# RPi_Bowler_Port.net
KiCad netlist of a schematic drawn in Altium Designer
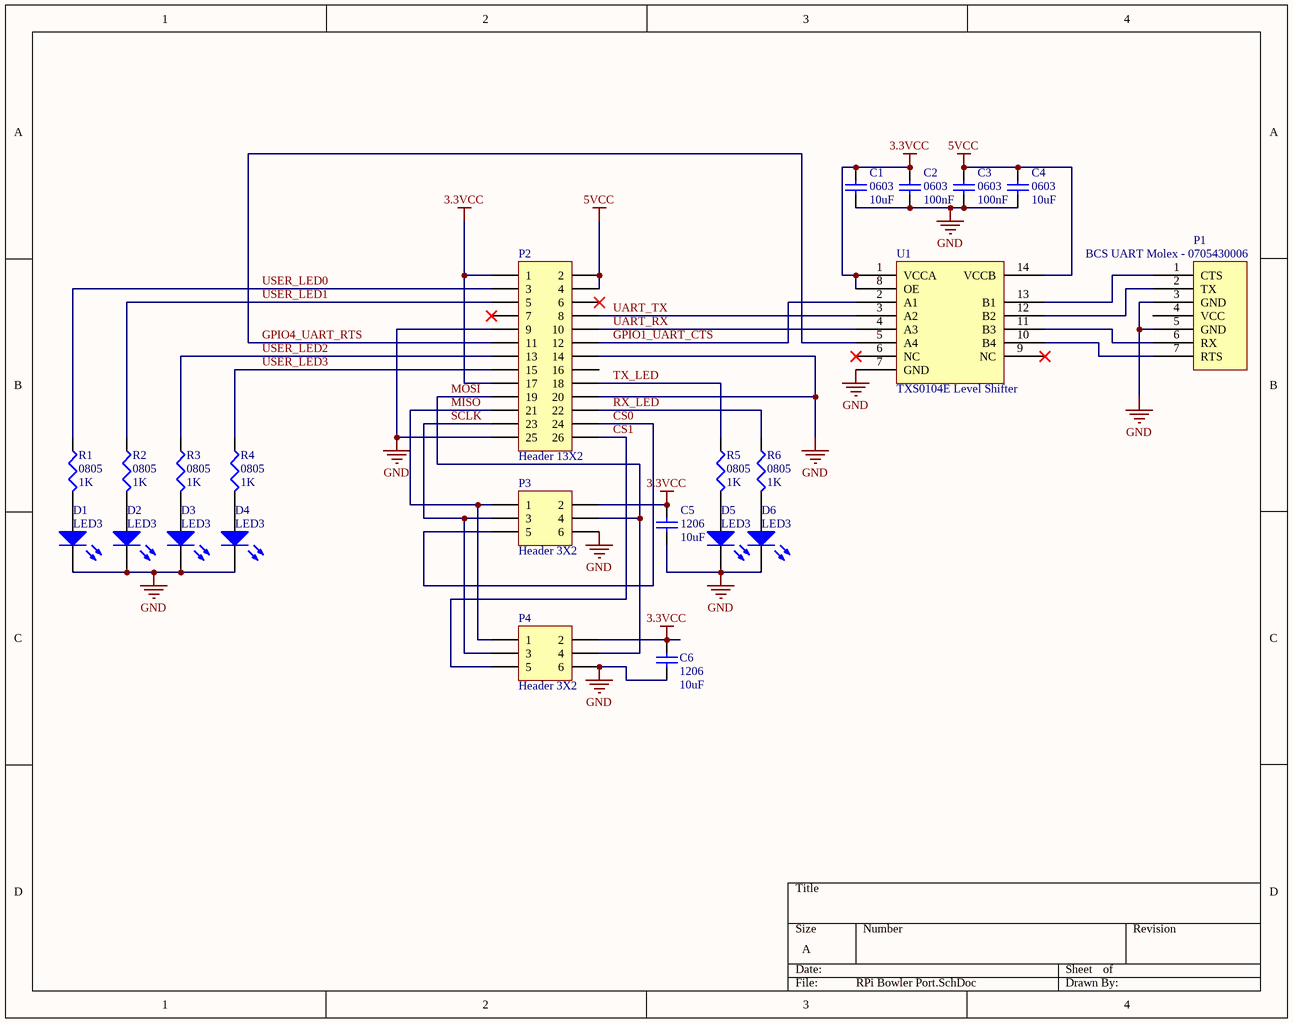
[diagram p0: RPi Bowler Port.SchDoc]

(export (version "E")
  (design (tool "Eeschema 10.0.6"))
  (components
    (comp (ref "C1")
      (value "0603")
      (footprint "1608[0603]")
      (description "Capacitor (Semiconductor SIM Model)")
      (fields (field (name "ALTIUM_VALUE") "10uF") (field (name "PUBLISHER") "Altium Limited"))
      (libsource (lib "Miscellaneous Devices") (part "Cap Semi"))
    )
    (comp (ref "C2")
      (value "0603")
      (footprint "1608[0603]")
      (description "Capacitor (Semiconductor SIM Model)")
      (fields (field (name "ALTIUM_VALUE") "100nF") (field (name "PUBLISHER") "Altium Limited"))
      (libsource (lib "Miscellaneous Devices") (part "Cap Semi"))
    )
    (comp (ref "C3")
      (value "0603")
      (footprint "1608[0603]")
      (description "Capacitor (Semiconductor SIM Model)")
      (fields (field (name "ALTIUM_VALUE") "100nF") (field (name "PUBLISHER") "Altium Limited"))
      (libsource (lib "Miscellaneous Devices") (part "Cap Semi"))
    )
    (comp (ref "C4")
      (value "0603")
      (footprint "1608[0603]")
      (description "Capacitor (Semiconductor SIM Model)")
      (fields (field (name "ALTIUM_VALUE") "10uF") (field (name "PUBLISHER") "Altium Limited"))
      (libsource (lib "Miscellaneous Devices") (part "Cap Semi"))
    )
    (comp (ref "C5")
      (value "1206")
      (footprint "C1206")
      (description "Capacitor (Semiconductor SIM Model)")
      (fields (field (name "ALTIUM_VALUE") "10uF") (field (name "PUBLISHER") "Altium Limited"))
      (libsource (lib "Miscellaneous Devices") (part "Cap Semi"))
    )
    (comp (ref "C6")
      (value "1206")
      (footprint "C1206")
      (description "Capacitor (Semiconductor SIM Model)")
      (fields (field (name "ALTIUM_VALUE") "10uF") (field (name "PUBLISHER") "Altium Limited"))
      (libsource (lib "Miscellaneous Devices") (part "Cap Semi"))
    )
    (comp (ref "D1")
      (value "LED3")
      (footprint "SM 0805 polarized")
      (description "Typical BLUE SiC LED")
      (fields (field (name "PUBLISHER") "Altium Limited"))
      (libsource (lib "Miscellaneous Devices") (part "LED3"))
    )
    (comp (ref "D2")
      (value "LED3")
      (footprint "SM 0805 polarized")
      (description "Typical BLUE SiC LED")
      (fields (field (name "PUBLISHER") "Altium Limited"))
      (libsource (lib "Miscellaneous Devices") (part "LED3"))
    )
    (comp (ref "D3")
      (value "LED3")
      (footprint "SM 0805 polarized")
      (description "Typical BLUE SiC LED")
      (fields (field (name "PUBLISHER") "Altium Limited"))
      (libsource (lib "Miscellaneous Devices") (part "LED3"))
    )
    (comp (ref "D4")
      (value "LED3")
      (footprint "SM 0805 polarized")
      (description "Typical BLUE SiC LED")
      (fields (field (name "PUBLISHER") "Altium Limited"))
      (libsource (lib "Miscellaneous Devices") (part "LED3"))
    )
    (comp (ref "D5")
      (value "LED3")
      (footprint "SM 0805 polarized")
      (description "Typical BLUE SiC LED")
      (fields (field (name "PUBLISHER") "Altium Limited"))
      (libsource (lib "Miscellaneous Devices") (part "LED3"))
    )
    (comp (ref "D6")
      (value "LED3")
      (footprint "SM 0805 polarized")
      (description "Typical BLUE SiC LED")
      (fields (field (name "PUBLISHER") "Altium Limited"))
      (libsource (lib "Miscellaneous Devices") (part "LED3"))
    )
    (comp (ref "P1")
      (value "BCS UART Molex - 0705430006")
      (footprint "BCS Serial Port - Molex")
      (description "BCS UART Port Molex")
      (libsource (lib "RPi Bowler Symbol Lib") (part "BCS Serial Port - Molex"))
    )
    (comp (ref "P2")
      (value "Header 13X2")
      (footprint "HDR2X13")
      (description "Header, 13-Pin, Dual row")
      (fields (field (name "PUBLISHER") "Altium Limited"))
      (libsource (lib "Miscellaneous Connectors") (part "Header 13X2"))
    )
    (comp (ref "P3")
      (value "Header 3X2")
      (footprint "HDR2X3")
      (description "Header, 3-Pin, Dual row")
      (fields (field (name "PUBLISHER") "Altium Limited"))
      (libsource (lib "Miscellaneous Connectors") (part "Header 3X2"))
    )
    (comp (ref "P4")
      (value "Header 3X2")
      (footprint "HDR2X3")
      (description "Header, 3-Pin, Dual row")
      (fields (field (name "PUBLISHER") "Altium Limited"))
      (libsource (lib "Miscellaneous Connectors") (part "Header 3X2"))
    )
    (comp (ref "R1")
      (value "0805")
      (footprint "SM 0805 - gap trimmed")
      (description "Resistor")
      (fields (field (name "ALTIUM_VALUE") "1K") (field (name "PUBLISHER") "Altium Limited"))
      (libsource (lib "Miscellaneous Devices") (part "Res3"))
    )
    (comp (ref "R2")
      (value "0805")
      (footprint "SM 0805 - gap trimmed")
      (description "Resistor")
      (fields (field (name "ALTIUM_VALUE") "1K") (field (name "PUBLISHER") "Altium Limited"))
      (libsource (lib "Miscellaneous Devices") (part "Res3"))
    )
    (comp (ref "R3")
      (value "0805")
      (footprint "SM 0805 - gap trimmed")
      (description "Resistor")
      (fields (field (name "ALTIUM_VALUE") "1K") (field (name "PUBLISHER") "Altium Limited"))
      (libsource (lib "Miscellaneous Devices") (part "Res3"))
    )
    (comp (ref "R4")
      (value "0805")
      (footprint "SM 0805 - gap trimmed")
      (description "Resistor")
      (fields (field (name "ALTIUM_VALUE") "1K") (field (name "PUBLISHER") "Altium Limited"))
      (libsource (lib "Miscellaneous Devices") (part "Res3"))
    )
    (comp (ref "R5")
      (value "0805")
      (footprint "SM 0805 - gap trimmed")
      (description "Resistor")
      (fields (field (name "ALTIUM_VALUE") "1K") (field (name "PUBLISHER") "Altium Limited"))
      (libsource (lib "Miscellaneous Devices") (part "Res3"))
    )
    (comp (ref "R6")
      (value "0805")
      (footprint "SM 0805 - gap trimmed")
      (description "Resistor")
      (fields (field (name "ALTIUM_VALUE") "1K") (field (name "PUBLISHER") "Altium Limited"))
      (libsource (lib "Miscellaneous Devices") (part "Res3"))
    )
    (comp (ref "U1")
      (value "TXS0104E Level Shifter")
      (footprint "RGY  (S-PVQFN-N14)")
      (description "TXS0104E - Bidriectional Opendrain/pushpull level shift")
      (libsource (lib "RPi Bowler Symbol Lib") (part "TXS0104E"))
    )
  )
  (nets
    (net (code "1") (name "/CS0") (class "Default")
      (node (ref "P2") (pin "24") (pinfunction "24_24") (pintype "passive"))
      (node (ref "P3") (pin "5") (pinfunction "5_5") (pintype "passive"))
    )
    (net (code "2") (name "/CS1") (class "Default")
      (node (ref "P2") (pin "26") (pinfunction "26_26") (pintype "passive"))
      (node (ref "P4") (pin "5") (pinfunction "5_5") (pintype "passive"))
    )
    (net (code "3") (name "/GPIO1_UART_CTS") (class "Default")
      (node (ref "P2") (pin "12") (pinfunction "12_12") (pintype "passive"))
      (node (ref "U1") (pin "2") (pinfunction "A1_2") (pintype "passive"))
    )
    (net (code "4") (name "/GPIO4_UART_RTS") (class "Default")
      (node (ref "P2") (pin "11") (pinfunction "11_11") (pintype "passive"))
      (node (ref "U1") (pin "5") (pinfunction "A4_5") (pintype "passive"))
    )
    (net (code "5") (name "/MISO") (class "Default")
      (node (ref "P2") (pin "21") (pinfunction "21_21") (pintype "passive"))
      (node (ref "P3") (pin "1") (pinfunction "1_1") (pintype "passive"))
      (node (ref "P4") (pin "1") (pinfunction "1_1") (pintype "passive"))
    )
    (net (code "6") (name "/MOSI") (class "Default")
      (node (ref "P2") (pin "19") (pinfunction "19_19") (pintype "passive"))
      (node (ref "P3") (pin "4") (pinfunction "4_4") (pintype "passive"))
      (node (ref "P4") (pin "4") (pinfunction "4_4") (pintype "passive"))
    )
    (net (code "7") (name "/RX_LED") (class "Default")
      (node (ref "P2") (pin "22") (pinfunction "22_22") (pintype "passive"))
      (node (ref "R6") (pin "1") (pinfunction "1_1") (pintype "passive"))
    )
    (net (code "8") (name "/SCLK") (class "Default")
      (node (ref "P2") (pin "23") (pinfunction "23_23") (pintype "passive"))
      (node (ref "P3") (pin "3") (pinfunction "3_3") (pintype "passive"))
      (node (ref "P4") (pin "3") (pinfunction "3_3") (pintype "passive"))
    )
    (net (code "9") (name "/TX_LED") (class "Default")
      (node (ref "P2") (pin "18") (pinfunction "18_18") (pintype "passive"))
      (node (ref "R5") (pin "1") (pinfunction "1_1") (pintype "passive"))
    )
    (net (code "10") (name "/UART_RX") (class "Default")
      (node (ref "P2") (pin "10") (pinfunction "10_10") (pintype "passive"))
      (node (ref "U1") (pin "4") (pinfunction "A3_4") (pintype "passive"))
    )
    (net (code "11") (name "/UART_TX") (class "Default")
      (node (ref "P2") (pin "8") (pinfunction "8_8") (pintype "passive"))
      (node (ref "U1") (pin "3") (pinfunction "A2_3") (pintype "passive"))
    )
    (net (code "12") (name "/USER_LED0") (class "Default")
      (node (ref "P2") (pin "3") (pinfunction "3_3") (pintype "passive"))
      (node (ref "R1") (pin "1") (pinfunction "1_1") (pintype "passive"))
    )
    (net (code "13") (name "/USER_LED1") (class "Default")
      (node (ref "P2") (pin "5") (pinfunction "5_5") (pintype "passive"))
      (node (ref "R2") (pin "1") (pinfunction "1_1") (pintype "passive"))
    )
    (net (code "14") (name "/USER_LED2") (class "Default")
      (node (ref "P2") (pin "13") (pinfunction "13_13") (pintype "passive"))
      (node (ref "R3") (pin "1") (pinfunction "1_1") (pintype "passive"))
    )
    (net (code "15") (name "/USER_LED3") (class "Default")
      (node (ref "P2") (pin "15") (pinfunction "15_15") (pintype "passive"))
      (node (ref "R4") (pin "1") (pinfunction "1_1") (pintype "passive"))
    )
    (net (code "16") (name "3.3VCC") (class "Default")
      (node (ref "C1") (pin "2") (pinfunction "2_2") (pintype "passive"))
      (node (ref "C2") (pin "2") (pinfunction "2_2") (pintype "passive"))
      (node (ref "C5") (pin "2") (pinfunction "2_2") (pintype "passive"))
      (node (ref "C6") (pin "2") (pinfunction "2_2") (pintype "passive"))
      (node (ref "P2") (pin "1") (pinfunction "1_1") (pintype "passive"))
      (node (ref "P2") (pin "17") (pinfunction "17_17") (pintype "passive"))
      (node (ref "P3") (pin "2") (pinfunction "2_2") (pintype "passive"))
      (node (ref "P4") (pin "2") (pinfunction "2_2") (pintype "passive"))
      (node (ref "U1") (pin "1") (pinfunction "VCCA_1") (pintype "passive"))
      (node (ref "U1") (pin "8") (pinfunction "OE_8") (pintype "passive"))
    )
    (net (code "17") (name "5VCC") (class "Default")
      (node (ref "C3") (pin "2") (pinfunction "2_2") (pintype "passive"))
      (node (ref "C4") (pin "2") (pinfunction "2_2") (pintype "passive"))
      (node (ref "P2") (pin "2") (pinfunction "2_2") (pintype "passive"))
      (node (ref "P2") (pin "4") (pinfunction "4_4") (pintype "passive"))
      (node (ref "U1") (pin "14") (pinfunction "VCCB_14") (pintype "passive"))
    )
    (net (code "18") (name "GND") (class "Default")
      (node (ref "C1") (pin "1") (pinfunction "1_1") (pintype "passive"))
      (node (ref "C2") (pin "1") (pinfunction "1_1") (pintype "passive"))
      (node (ref "C3") (pin "1") (pinfunction "1_1") (pintype "passive"))
      (node (ref "C4") (pin "1") (pinfunction "1_1") (pintype "passive"))
      (node (ref "C5") (pin "1") (pinfunction "1_1") (pintype "passive"))
      (node (ref "C6") (pin "1") (pinfunction "1_1") (pintype "passive"))
      (node (ref "D1") (pin "1") (pinfunction "A_1") (pintype "passive"))
      (node (ref "D2") (pin "1") (pinfunction "A_1") (pintype "passive"))
      (node (ref "D3") (pin "1") (pinfunction "A_1") (pintype "passive"))
      (node (ref "D4") (pin "1") (pinfunction "A_1") (pintype "passive"))
      (node (ref "D5") (pin "1") (pinfunction "A_1") (pintype "passive"))
      (node (ref "D6") (pin "1") (pinfunction "A_1") (pintype "passive"))
      (node (ref "P1") (pin "3") (pinfunction "GND_3") (pintype "passive"))
      (node (ref "P1") (pin "5") (pinfunction "GND_5") (pintype "passive"))
      (node (ref "P2") (pin "14") (pinfunction "14_14") (pintype "passive"))
      (node (ref "P2") (pin "20") (pinfunction "20_20") (pintype "passive"))
      (node (ref "P2") (pin "25") (pinfunction "25_25") (pintype "passive"))
      (node (ref "P2") (pin "9") (pinfunction "9_9") (pintype "passive"))
      (node (ref "P3") (pin "6") (pinfunction "6_6") (pintype "passive"))
      (node (ref "P4") (pin "6") (pinfunction "6_6") (pintype "passive"))
      (node (ref "U1") (pin "7") (pinfunction "GND_7") (pintype "passive"))
    )
    (net (code "19") (name "Net-(D1-K)") (class "Default")
      (node (ref "D1") (pin "2") (pinfunction "K_2") (pintype "passive"))
      (node (ref "R1") (pin "2") (pinfunction "2_2") (pintype "passive"))
    )
    (net (code "20") (name "Net-(D2-K)") (class "Default")
      (node (ref "D2") (pin "2") (pinfunction "K_2") (pintype "passive"))
      (node (ref "R2") (pin "2") (pinfunction "2_2") (pintype "passive"))
    )
    (net (code "21") (name "Net-(D3-K)") (class "Default")
      (node (ref "D3") (pin "2") (pinfunction "K_2") (pintype "passive"))
      (node (ref "R3") (pin "2") (pinfunction "2_2") (pintype "passive"))
    )
    (net (code "22") (name "Net-(D4-K)") (class "Default")
      (node (ref "D4") (pin "2") (pinfunction "K_2") (pintype "passive"))
      (node (ref "R4") (pin "2") (pinfunction "2_2") (pintype "passive"))
    )
    (net (code "23") (name "Net-(D5-K)") (class "Default")
      (node (ref "D5") (pin "2") (pinfunction "K_2") (pintype "passive"))
      (node (ref "R5") (pin "2") (pinfunction "2_2") (pintype "passive"))
    )
    (net (code "24") (name "Net-(D6-K)") (class "Default")
      (node (ref "D6") (pin "2") (pinfunction "K_2") (pintype "passive"))
      (node (ref "R6") (pin "2") (pinfunction "2_2") (pintype "passive"))
    )
    (net (code "25") (name "Net-(P1-CTS)") (class "Default")
      (node (ref "P1") (pin "1") (pinfunction "CTS_1") (pintype "passive"))
      (node (ref "U1") (pin "13") (pinfunction "B1_13") (pintype "passive"))
    )
    (net (code "26") (name "Net-(P1-RTS)") (class "Default")
      (node (ref "P1") (pin "7") (pinfunction "RTS_7") (pintype "passive"))
      (node (ref "U1") (pin "10") (pinfunction "B4_10") (pintype "passive"))
    )
    (net (code "27") (name "Net-(P1-RX)") (class "Default")
      (node (ref "P1") (pin "6") (pinfunction "RX_6") (pintype "passive"))
      (node (ref "U1") (pin "11") (pinfunction "B3_11") (pintype "passive"))
    )
    (net (code "28") (name "Net-(P1-TX)") (class "Default")
      (node (ref "P1") (pin "2") (pinfunction "TX_2") (pintype "passive"))
      (node (ref "U1") (pin "12") (pinfunction "B2_12") (pintype "passive"))
    )
    (net (code "29") (name "unconnected-(P1-VCC-Pad4)") (class "Default")
      (node (ref "P1") (pin "4") (pinfunction "VCC_4") (pintype "passive"))
    )
    (net (code "30") (name "unconnected-(P2-Pad6)") (class "Default")
      (node (ref "P2") (pin "6") (pinfunction "6_6") (pintype "passive+no_connect"))
    )
    (net (code "31") (name "unconnected-(P2-Pad7)") (class "Default")
      (node (ref "P2") (pin "7") (pinfunction "7_7") (pintype "passive+no_connect"))
    )
    (net (code "32") (name "unconnected-(P2-Pad16)") (class "Default")
      (node (ref "P2") (pin "16") (pinfunction "16_16") (pintype "passive"))
    )
    (net (code "33") (name "unconnected-(U1-NC-Pad6)") (class "Default")
      (node (ref "U1") (pin "6") (pinfunction "NC_6") (pintype "passive+no_connect"))
    )
    (net (code "34") (name "unconnected-(U1-NC-Pad9)") (class "Default")
      (node (ref "U1") (pin "9") (pinfunction "NC_9") (pintype "passive+no_connect"))
    )
  )
)
